# Agua.net
KiCad netlist of a schematic drawn in EAGLE
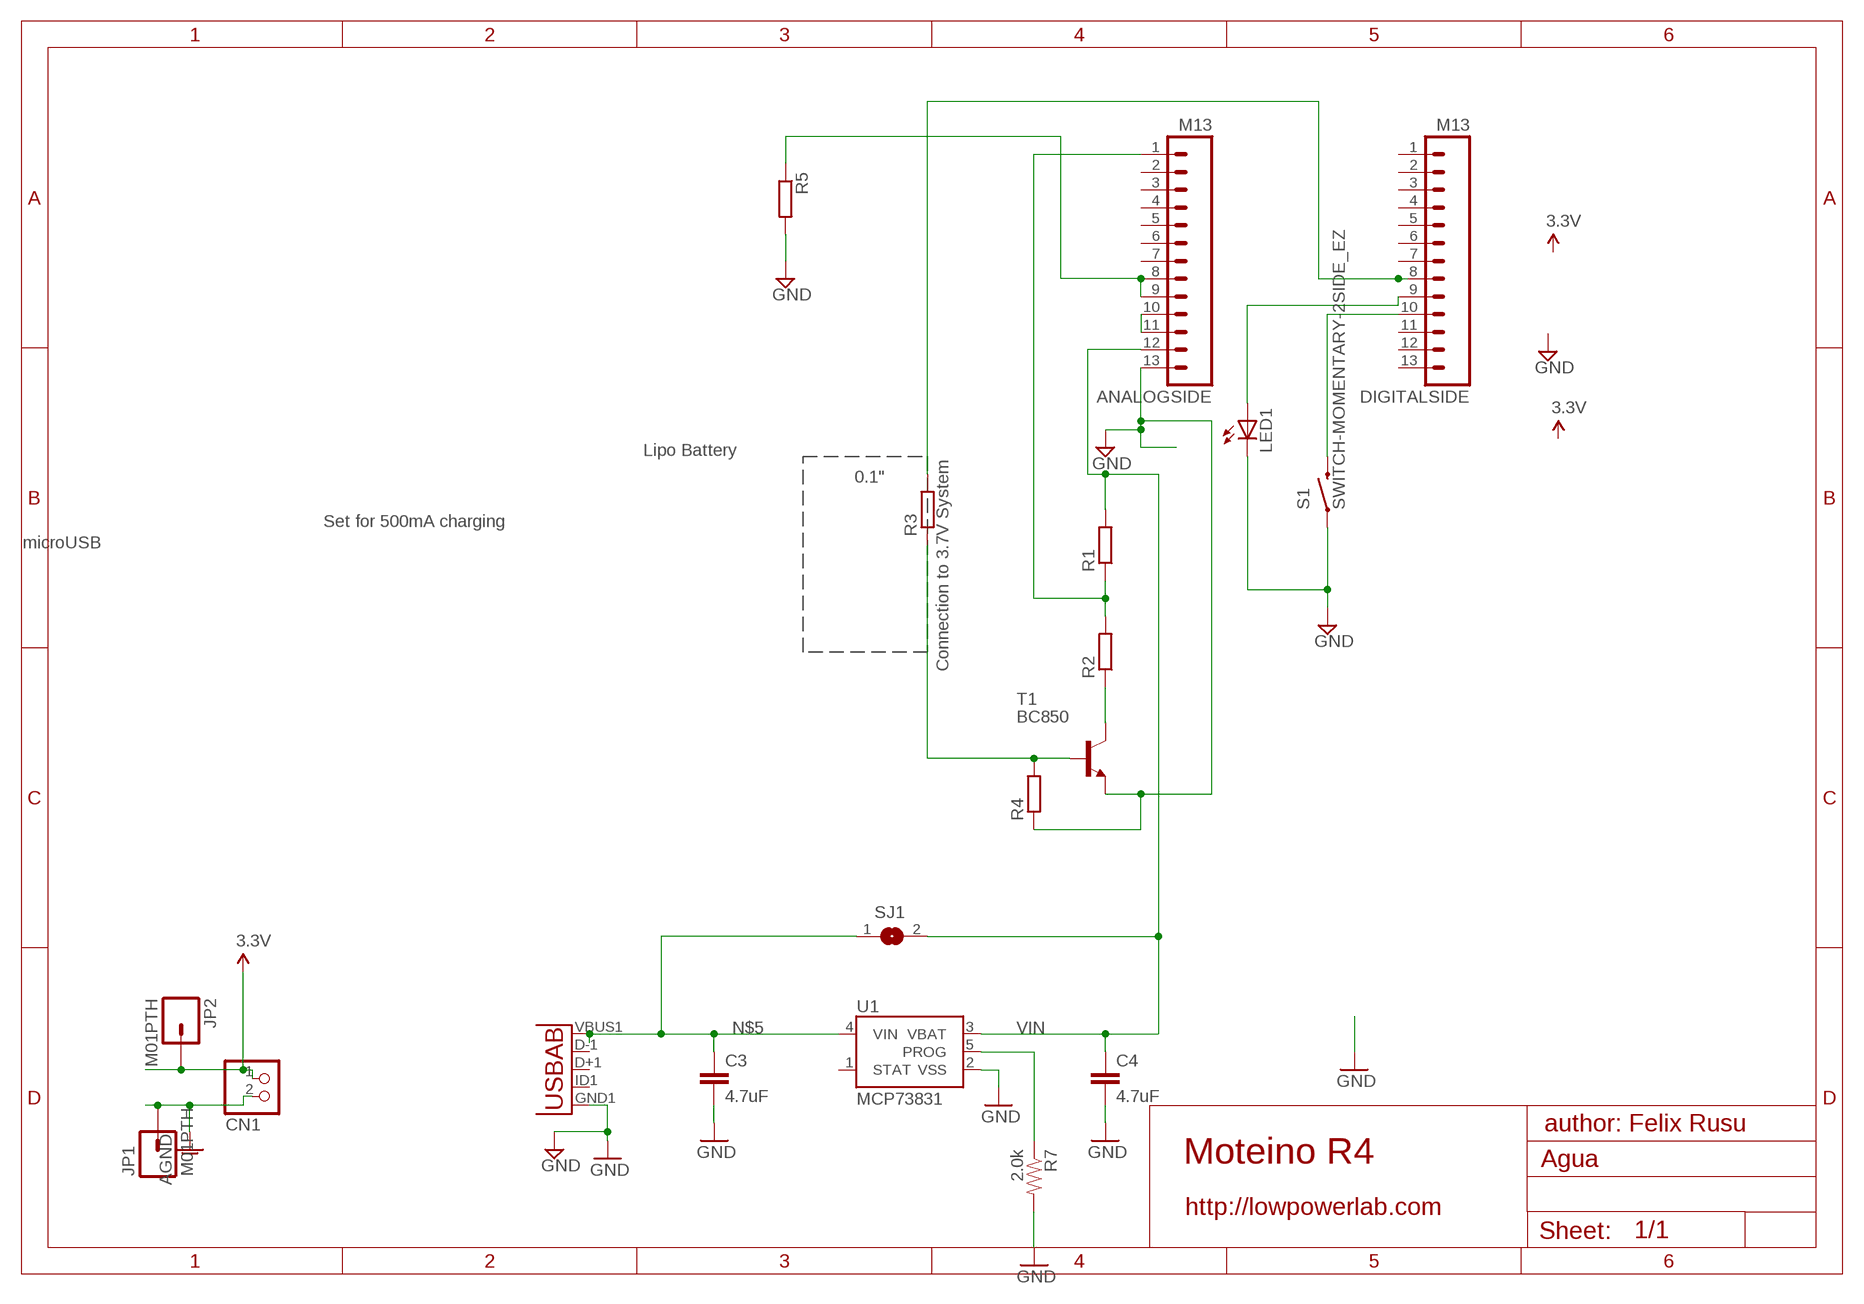
[diagram p0: schematic, sheet 1]

(export (version "E")
  (design (tool "Eeschema 10.0.6"))
  (components
    (comp (ref "ANALOGSIDE")
      (value "M13")
      (footprint "eagle-import:1X13")
      (libsource (lib "eagle-import") (part "M13"))
    )
    (comp (ref "C3")
      (value "4.7uF")
      (footprint "eagle-import:0603-CAP")
      (libsource (lib "eagle-import") (part "4.7UF-6.3V-10%(0603)0603"))
    )
    (comp (ref "C4")
      (value "4.7uF")
      (footprint "eagle-import:0603-CAP")
      (libsource (lib "eagle-import") (part "4.7UF-6.3V-10%(0603)0603"))
    )
    (comp (ref "CN1")
      (value "JST_2PIN-SMT")
      (footprint "eagle-import:JST-PH-2-SMT")
      (libsource (lib "eagle-import") (part "JST_2PIN-SMT"))
    )
    (comp (ref "DIGITALSIDE")
      (value "M13")
      (footprint "eagle-import:1X13")
      (libsource (lib "eagle-import") (part "M13"))
    )
    (comp (ref "JP1")
      (value "M01PTH")
      (footprint "eagle-import:1X01")
      (libsource (lib "eagle-import") (part "M01PTH"))
    )
    (comp (ref "JP2")
      (value "M01PTH")
      (footprint "eagle-import:1X01")
      (libsource (lib "eagle-import") (part "M01PTH"))
    )
    (comp (ref "JP9")
      (value "Micro USB")
      (footprint "eagle-import:USB-AB-MICRO-SMD_V03")
      (libsource (lib "eagle-import") (part "USB-ABCONN-11794"))
    )
    (comp (ref "LED1")
      (value "LED3MM")
      (footprint "eagle-import:LED3MM")
      (libsource (lib "eagle-import") (part "LED3MM"))
    )
    (comp (ref "R1")
      (value "R-EU_0204/7")
      (footprint "eagle-import:0204_7")
      (libsource (lib "eagle-import") (part "R-EU_0204/7"))
    )
    (comp (ref "R2")
      (value "R-EU_0204/7")
      (footprint "eagle-import:0204_7")
      (libsource (lib "eagle-import") (part "R-EU_0204/7"))
    )
    (comp (ref "R3")
      (value "R-EU_M1206")
      (footprint "eagle-import:M1206")
      (libsource (lib "eagle-import") (part "R-EU_M1206"))
    )
    (comp (ref "R4")
      (value "R-EU_M1206")
      (footprint "eagle-import:M1206")
      (libsource (lib "eagle-import") (part "R-EU_M1206"))
    )
    (comp (ref "R5")
      (value "R-EU_0204/7")
      (footprint "eagle-import:0204_7")
      (libsource (lib "eagle-import") (part "R-EU_0204/7"))
    )
    (comp (ref "R7")
      (value "2.0k")
      (footprint "eagle-import:0603-RES")
      (libsource (lib "eagle-import") (part "2.0KOHM1/10W5%(0603)"))
    )
    (comp (ref "S1")
      (value "SWITCH-MOMENTARY-2SIDE_EZ")
      (footprint "eagle-import:TACTILE-PTH-SIDEEZ")
      (libsource (lib "eagle-import") (part "SWITCH-MOMENTARY-2SIDE_EZ"))
    )
    (comp (ref "SJ1") (value "SJ") (footprint "eagle-import:SJ") (libsource (lib "eagle-import") (part "SJ")))
    (comp (ref "T1")
      (value "BC850")
      (footprint "eagle-import:SOT23")
      (libsource (lib "eagle-import") (part "BC850"))
    )
    (comp (ref "U1")
      (value "MCP73831")
      (footprint "eagle-import:SOT23-5")
      (libsource (lib "eagle-import") (part "MCP73831"))
    )
  )
  (nets
    (net (code "1") (name "/N$5") (class "Default")
      (node (ref "C3") (pin "1") (pinfunction "1_1") (pintype "passive"))
      (node (ref "JP9") (pin "VBUS1") (pinfunction "VBUS_VBUS1") (pintype "bidirectional"))
      (node (ref "SJ1") (pin "1") (pinfunction "1_1") (pintype "passive"))
      (node (ref "U1") (pin "4") (pinfunction "VIN_4") (pintype "power_in"))
    )
    (net (code "2") (name "/VIN") (class "Default")
      (node (ref "ANALOGSIDE") (pin "12") (pinfunction "12_12") (pintype "passive"))
      (node (ref "C4") (pin "1") (pinfunction "1_1") (pintype "passive"))
      (node (ref "R1") (pin "2") (pinfunction "2_2") (pintype "passive"))
      (node (ref "SJ1") (pin "2") (pinfunction "2_2") (pintype "passive"))
      (node (ref "U1") (pin "3") (pinfunction "VBAT_3") (pintype "power_in"))
    )
    (net (code "3") (name "3.3V") (class "Default")
      (node (ref "CN1") (pin "1") (pinfunction "2_1") (pintype "passive"))
      (node (ref "JP2") (pin "1") (pinfunction "1_1") (pintype "passive"))
    )
    (net (code "4") (name "AGND") (class "Default")
      (node (ref "CN1") (pin "2") (pinfunction "1_2") (pintype "passive"))
      (node (ref "JP1") (pin "1") (pinfunction "1_1") (pintype "passive"))
    )
    (net (code "5") (name "GND") (class "Default")
      (node (ref "ANALOGSIDE") (pin "13") (pinfunction "13_13") (pintype "passive"))
      (node (ref "C3") (pin "2") (pinfunction "2_2") (pintype "passive"))
      (node (ref "C4") (pin "2") (pinfunction "2_2") (pintype "passive"))
      (node (ref "JP9") (pin "GND1") (pinfunction "GND_GND1") (pintype "bidirectional"))
      (node (ref "LED1") (pin "K") (pinfunction "C_K") (pintype "passive"))
      (node (ref "R4") (pin "1") (pinfunction "1_1") (pintype "passive"))
      (node (ref "R5") (pin "2") (pinfunction "2_2") (pintype "passive"))
      (node (ref "R7") (pin "2") (pinfunction "2_2") (pintype "passive"))
      (node (ref "S1") (pin "1") (pinfunction "1_1") (pintype "passive"))
      (node (ref "T1") (pin "2") (pinfunction "E_2") (pintype "passive"))
      (node (ref "U1") (pin "2") (pinfunction "VSS_2") (pintype "power_in"))
    )
    (net (code "6") (name "Net-(ANALOGSIDE-Pad1)") (class "Default")
      (node (ref "ANALOGSIDE") (pin "1") (pinfunction "1_1") (pintype "passive"))
      (node (ref "R1") (pin "1") (pinfunction "1_1") (pintype "passive"))
      (node (ref "R2") (pin "2") (pinfunction "2_2") (pintype "passive"))
    )
    (net (code "7") (name "Net-(ANALOGSIDE-Pad8)") (class "Default")
      (node (ref "ANALOGSIDE") (pin "8") (pinfunction "8_8") (pintype "passive"))
      (node (ref "ANALOGSIDE") (pin "9") (pinfunction "9_9") (pintype "passive"))
      (node (ref "R5") (pin "1") (pinfunction "1_1") (pintype "passive"))
    )
    (net (code "8") (name "Net-(ANALOGSIDE-Pad10)") (class "Default")
      (node (ref "ANALOGSIDE") (pin "10") (pinfunction "10_10") (pintype "passive"))
      (node (ref "ANALOGSIDE") (pin "11") (pinfunction "11_11") (pintype "passive"))
    )
    (net (code "9") (name "Net-(DIGITALSIDE-Pad8)") (class "Default")
      (node (ref "DIGITALSIDE") (pin "8") (pinfunction "8_8") (pintype "passive"))
      (node (ref "R3") (pin "2") (pinfunction "2_2") (pintype "passive"))
    )
    (net (code "10") (name "Net-(DIGITALSIDE-Pad9)") (class "Default")
      (node (ref "DIGITALSIDE") (pin "9") (pinfunction "9_9") (pintype "passive"))
      (node (ref "LED1") (pin "A") (pinfunction "A_A") (pintype "passive"))
    )
    (net (code "11") (name "Net-(DIGITALSIDE-Pad10)") (class "Default")
      (node (ref "DIGITALSIDE") (pin "10") (pinfunction "10_10") (pintype "passive"))
      (node (ref "S1") (pin "2") (pinfunction "2_2") (pintype "passive"))
    )
    (net (code "12") (name "Net-(T1-B)") (class "Default")
      (node (ref "R3") (pin "1") (pinfunction "1_1") (pintype "passive"))
      (node (ref "R4") (pin "2") (pinfunction "2_2") (pintype "passive"))
      (node (ref "T1") (pin "1") (pinfunction "B_1") (pintype "passive"))
    )
    (net (code "13") (name "Net-(T1-C)") (class "Default")
      (node (ref "R2") (pin "1") (pinfunction "1_1") (pintype "passive"))
      (node (ref "T1") (pin "3") (pinfunction "C_3") (pintype "passive"))
    )
    (net (code "14") (name "Net-(U1-PROG)") (class "Default")
      (node (ref "R7") (pin "1") (pinfunction "1_1") (pintype "passive"))
      (node (ref "U1") (pin "5") (pinfunction "PROG_5") (pintype "input"))
    )
    (net (code "15") (name "unconnected-(ANALOGSIDE-Pad2)") (class "Default")
      (node (ref "ANALOGSIDE") (pin "2") (pinfunction "2_2") (pintype "passive"))
    )
    (net (code "16") (name "unconnected-(ANALOGSIDE-Pad3)") (class "Default")
      (node (ref "ANALOGSIDE") (pin "3") (pinfunction "3_3") (pintype "passive"))
    )
    (net (code "17") (name "unconnected-(ANALOGSIDE-Pad4)") (class "Default")
      (node (ref "ANALOGSIDE") (pin "4") (pinfunction "4_4") (pintype "passive"))
    )
    (net (code "18") (name "unconnected-(ANALOGSIDE-Pad5)") (class "Default")
      (node (ref "ANALOGSIDE") (pin "5") (pinfunction "5_5") (pintype "passive"))
    )
    (net (code "19") (name "unconnected-(ANALOGSIDE-Pad6)") (class "Default")
      (node (ref "ANALOGSIDE") (pin "6") (pinfunction "6_6") (pintype "passive"))
    )
    (net (code "20") (name "unconnected-(ANALOGSIDE-Pad7)") (class "Default")
      (node (ref "ANALOGSIDE") (pin "7") (pinfunction "7_7") (pintype "passive"))
    )
    (net (code "21") (name "unconnected-(DIGITALSIDE-Pad1)") (class "Default")
      (node (ref "DIGITALSIDE") (pin "1") (pinfunction "1_1") (pintype "passive"))
    )
    (net (code "22") (name "unconnected-(DIGITALSIDE-Pad2)") (class "Default")
      (node (ref "DIGITALSIDE") (pin "2") (pinfunction "2_2") (pintype "passive"))
    )
    (net (code "23") (name "unconnected-(DIGITALSIDE-Pad3)") (class "Default")
      (node (ref "DIGITALSIDE") (pin "3") (pinfunction "3_3") (pintype "passive"))
    )
    (net (code "24") (name "unconnected-(DIGITALSIDE-Pad4)") (class "Default")
      (node (ref "DIGITALSIDE") (pin "4") (pinfunction "4_4") (pintype "passive"))
    )
    (net (code "25") (name "unconnected-(DIGITALSIDE-Pad5)") (class "Default")
      (node (ref "DIGITALSIDE") (pin "5") (pinfunction "5_5") (pintype "passive"))
    )
    (net (code "26") (name "unconnected-(DIGITALSIDE-Pad6)") (class "Default")
      (node (ref "DIGITALSIDE") (pin "6") (pinfunction "6_6") (pintype "passive"))
    )
    (net (code "27") (name "unconnected-(DIGITALSIDE-Pad7)") (class "Default")
      (node (ref "DIGITALSIDE") (pin "7") (pinfunction "7_7") (pintype "passive"))
    )
    (net (code "28") (name "unconnected-(DIGITALSIDE-Pad11)") (class "Default")
      (node (ref "DIGITALSIDE") (pin "11") (pinfunction "11_11") (pintype "passive"))
    )
    (net (code "29") (name "unconnected-(DIGITALSIDE-Pad12)") (class "Default")
      (node (ref "DIGITALSIDE") (pin "12") (pinfunction "12_12") (pintype "passive"))
    )
    (net (code "30") (name "unconnected-(DIGITALSIDE-Pad13)") (class "Default")
      (node (ref "DIGITALSIDE") (pin "13") (pinfunction "13_13") (pintype "passive"))
    )
    (net (code "31") (name "unconnected-(JP9-D+-PadD+1)") (class "Default")
      (node (ref "JP9") (pin "D+1") (pinfunction "D+_D+1") (pintype "bidirectional"))
    )
    (net (code "32") (name "unconnected-(JP9-D--PadD-1)") (class "Default")
      (node (ref "JP9") (pin "D-1") (pinfunction "D-_D-1") (pintype "bidirectional"))
    )
    (net (code "33") (name "unconnected-(JP9-USBID-PadID1)") (class "Default")
      (node (ref "JP9") (pin "ID1") (pinfunction "USBID_ID1") (pintype "bidirectional"))
    )
    (net (code "34") (name "unconnected-(U1-STAT-Pad1)") (class "Default")
      (node (ref "U1") (pin "1") (pinfunction "STAT_1") (pintype "output"))
    )
  )
)
